# micro.net
KiCad netlist of a schematic drawn in EAGLE
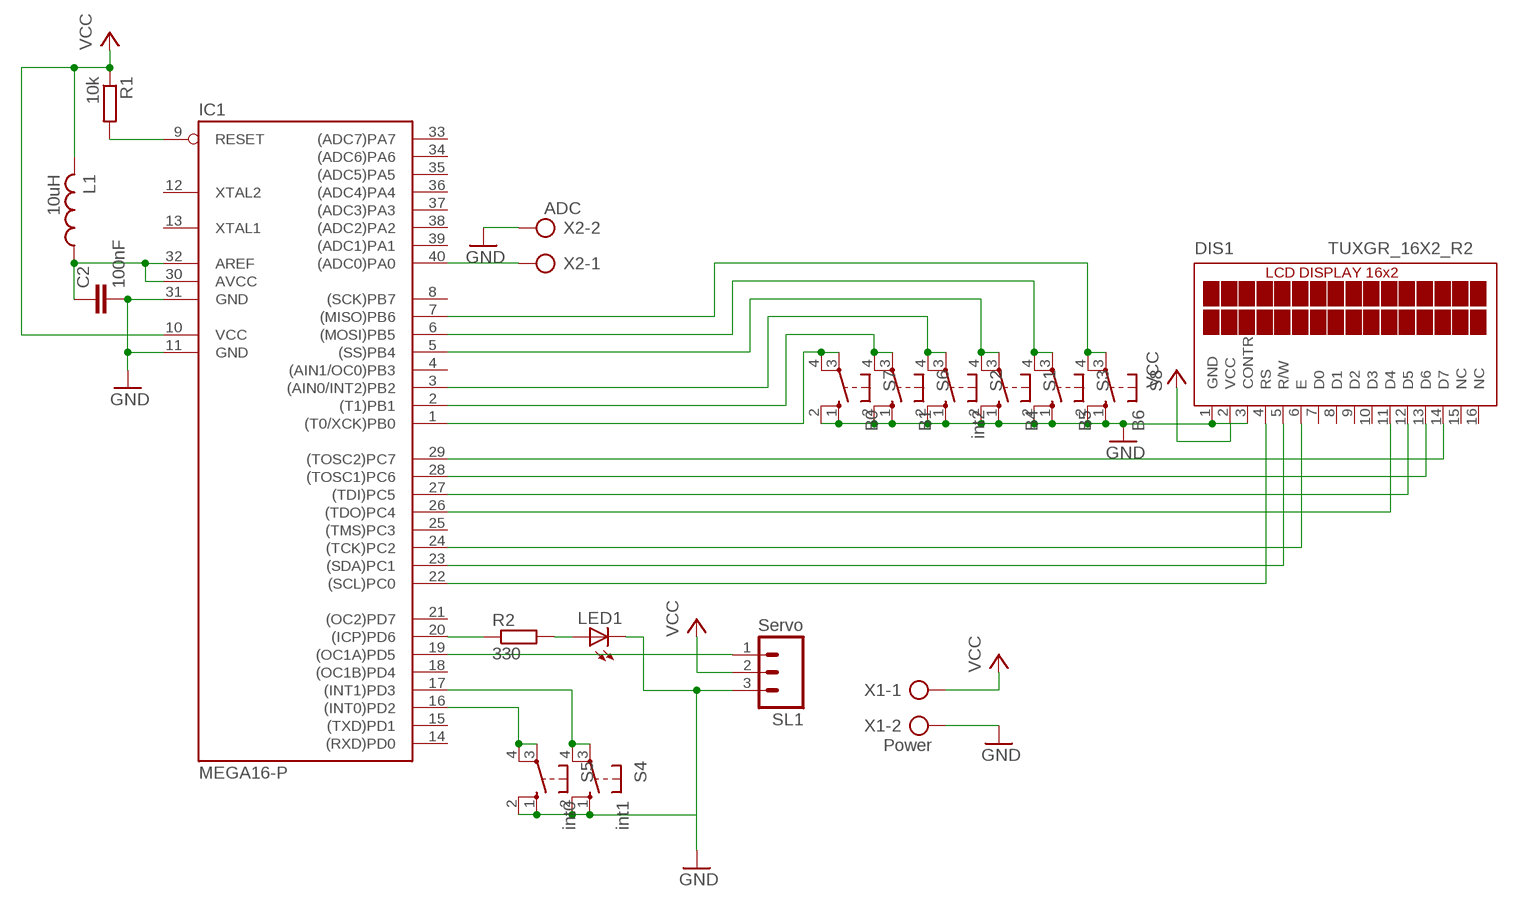
[diagram p0: schematic, sheet 1]

(export (version "E")
  (design (tool "Eeschema 10.0.6"))
  (components
    (comp (ref "C2")
      (value "100nF")
      (footprint "eagle-import:C025-024X044")
      (libsource (lib "eagle-import") (part "C-EU025-024X044"))
    )
    (comp (ref "DIS1")
      (value "TUXGR_16X2_R2")
      (footprint "eagle-import:TUXGR_16X2_R2")
      (libsource (lib "eagle-import") (part "TUXGR_16X2_R2"))
    )
    (comp (ref "IC1")
      (value "MEGA16-P")
      (footprint "eagle-import:DIL40")
      (fields (field (name "MPN") "ATMEGA16-16PU"))
      (libsource (lib "eagle-import") (part "MEGA16-P"))
    )
    (comp (ref "L1")
      (value "10uH")
      (footprint "eagle-import:0204_5")
      (libsource (lib "eagle-import") (part "L-US0204/5"))
    )
    (comp (ref "LED1")
      (value "LED5MM")
      (footprint "eagle-import:LED5MM")
      (libsource (lib "eagle-import") (part "LED5MM"))
    )
    (comp (ref "R1")
      (value "10k")
      (footprint "eagle-import:0204_7")
      (libsource (lib "eagle-import") (part "R-EU_0204/7"))
    )
    (comp (ref "R2")
      (value "330")
      (footprint "eagle-import:0204_7")
      (libsource (lib "eagle-import") (part "R-EU_0204/7"))
    )
    (comp (ref "S1")
      (value "B4")
      (footprint "eagle-import:B3F-10XX")
      (fields (field (name "MPN") "B3F-1000"))
      (libsource (lib "eagle-import") (part "10-XX"))
    )
    (comp (ref "S2")
      (value "int2")
      (footprint "eagle-import:B3F-10XX")
      (fields (field (name "MPN") "B3F-1000"))
      (libsource (lib "eagle-import") (part "10-XX"))
    )
    (comp (ref "S3")
      (value "B5")
      (footprint "eagle-import:B3F-10XX")
      (fields (field (name "MPN") "B3F-1000"))
      (libsource (lib "eagle-import") (part "10-XX"))
    )
    (comp (ref "S4")
      (value "int1")
      (footprint "eagle-import:B3F-10XX")
      (fields (field (name "MPN") "B3F-1000"))
      (libsource (lib "eagle-import") (part "10-XX"))
    )
    (comp (ref "S5")
      (value "int0")
      (footprint "eagle-import:B3F-10XX")
      (fields (field (name "MPN") "B3F-1000"))
      (libsource (lib "eagle-import") (part "10-XX"))
    )
    (comp (ref "S6")
      (value "B1")
      (footprint "eagle-import:B3F-10XX")
      (fields (field (name "MPN") "B3F-1000"))
      (libsource (lib "eagle-import") (part "10-XX"))
    )
    (comp (ref "S7")
      (value "B0")
      (footprint "eagle-import:B3F-10XX")
      (fields (field (name "MPN") "B3F-1000"))
      (libsource (lib "eagle-import") (part "10-XX"))
    )
    (comp (ref "S8")
      (value "B6")
      (footprint "eagle-import:B3F-10XX")
      (fields (field (name "MPN") "B3F-1000"))
      (libsource (lib "eagle-import") (part "10-XX"))
    )
    (comp (ref "SL1")
      (value "Servo")
      (footprint "eagle-import:03P")
      (libsource (lib "eagle-import") (part "M03"))
    )
    (comp (ref "X1")
      (value "Power")
      (footprint "eagle-import:AK300_2")
      (libsource (lib "eagle-import") (part "AK300/2"))
    )
    (comp (ref "X2")
      (value "ADC")
      (footprint "eagle-import:AK300_2")
      (libsource (lib "eagle-import") (part "AK300/2"))
    )
  )
  (nets
    (net (code "1") (name "GND") (class "Default")
      (node (ref "C2") (pin "2") (pinfunction "2_2") (pintype "passive"))
      (node (ref "DIS1") (pin "1") (pinfunction "GND_1") (pintype "power_in"))
      (node (ref "DIS1") (pin "3") (pinfunction "CONTR_3") (pintype "input"))
      (node (ref "IC1") (pin "11") (pinfunction "GND_11") (pintype "power_in"))
      (node (ref "IC1") (pin "31") (pinfunction "GND_31") (pintype "power_in"))
      (node (ref "LED1") (pin "K") (pinfunction "C_K") (pintype "passive"))
      (node (ref "S1") (pin "1") (pinfunction "S_1") (pintype "passive"))
      (node (ref "S1") (pin "2") (pinfunction "S1_2") (pintype "passive"))
      (node (ref "S2") (pin "1") (pinfunction "S_1") (pintype "passive"))
      (node (ref "S2") (pin "2") (pinfunction "S1_2") (pintype "passive"))
      (node (ref "S3") (pin "1") (pinfunction "S_1") (pintype "passive"))
      (node (ref "S3") (pin "2") (pinfunction "S1_2") (pintype "passive"))
      (node (ref "S4") (pin "1") (pinfunction "S_1") (pintype "passive"))
      (node (ref "S4") (pin "2") (pinfunction "S1_2") (pintype "passive"))
      (node (ref "S5") (pin "1") (pinfunction "S_1") (pintype "passive"))
      (node (ref "S5") (pin "2") (pinfunction "S1_2") (pintype "passive"))
      (node (ref "S6") (pin "1") (pinfunction "S_1") (pintype "passive"))
      (node (ref "S6") (pin "2") (pinfunction "S1_2") (pintype "passive"))
      (node (ref "S7") (pin "1") (pinfunction "S_1") (pintype "passive"))
      (node (ref "S7") (pin "2") (pinfunction "S1_2") (pintype "passive"))
      (node (ref "S8") (pin "1") (pinfunction "S_1") (pintype "passive"))
      (node (ref "S8") (pin "2") (pinfunction "S1_2") (pintype "passive"))
      (node (ref "SL1") (pin "3") (pinfunction "3_3") (pintype "passive"))
      (node (ref "X1") (pin "2") (pinfunction "KL_2") (pintype "passive"))
      (node (ref "X2") (pin "2") (pinfunction "KL_2") (pintype "passive"))
    )
    (net (code "2") (name "Net-(DIS1-D4)") (class "Default")
      (node (ref "DIS1") (pin "11") (pinfunction "D4_11") (pintype "input"))
      (node (ref "IC1") (pin "26") (pinfunction "(TDO)PC4_26") (pintype "bidirectional"))
    )
    (net (code "3") (name "Net-(DIS1-D5)") (class "Default")
      (node (ref "DIS1") (pin "12") (pinfunction "D5_12") (pintype "input"))
      (node (ref "IC1") (pin "27") (pinfunction "(TDI)PC5_27") (pintype "bidirectional"))
    )
    (net (code "4") (name "Net-(DIS1-D6)") (class "Default")
      (node (ref "DIS1") (pin "13") (pinfunction "D6_13") (pintype "input"))
      (node (ref "IC1") (pin "28") (pinfunction "(TOSC1)PC6_28") (pintype "bidirectional"))
    )
    (net (code "5") (name "Net-(DIS1-D7)") (class "Default")
      (node (ref "DIS1") (pin "14") (pinfunction "D7_14") (pintype "input"))
      (node (ref "IC1") (pin "29") (pinfunction "(TOSC2)PC7_29") (pintype "bidirectional"))
    )
    (net (code "6") (name "Net-(DIS1-E)") (class "Default")
      (node (ref "DIS1") (pin "6") (pinfunction "E_6") (pintype "input"))
      (node (ref "IC1") (pin "24") (pinfunction "(TCK)PC2_24") (pintype "bidirectional"))
    )
    (net (code "7") (name "Net-(DIS1-RS)") (class "Default")
      (node (ref "DIS1") (pin "4") (pinfunction "RS_4") (pintype "input"))
      (node (ref "IC1") (pin "22") (pinfunction "(SCL)PC0_22") (pintype "bidirectional"))
    )
    (net (code "8") (name "Net-(DIS1-R{slash}W)") (class "Default")
      (node (ref "DIS1") (pin "5") (pinfunction "R/W_5") (pintype "input"))
      (node (ref "IC1") (pin "23") (pinfunction "(SDA)PC1_23") (pintype "bidirectional"))
    )
    (net (code "9") (name "Net-(IC1-(ADC0)PA0)") (class "Default")
      (node (ref "IC1") (pin "40") (pinfunction "(ADC0)PA0_40") (pintype "bidirectional"))
      (node (ref "X2") (pin "1") (pinfunction "KL_1") (pintype "passive"))
    )
    (net (code "10") (name "Net-(IC1-(AIN0{slash}INT2)PB2)") (class "Default")
      (node (ref "IC1") (pin "3") (pinfunction "(AIN0/INT2)PB2_3") (pintype "bidirectional"))
      (node (ref "S2") (pin "3") (pinfunction "P_3") (pintype "passive"))
      (node (ref "S2") (pin "4") (pinfunction "P1_4") (pintype "passive"))
    )
    (net (code "11") (name "Net-(IC1-(ICP)PD6)") (class "Default")
      (node (ref "IC1") (pin "20") (pinfunction "(ICP)PD6_20") (pintype "bidirectional"))
      (node (ref "R2") (pin "1") (pinfunction "1_1") (pintype "passive"))
    )
    (net (code "12") (name "Net-(IC1-(INT0)PD2)") (class "Default")
      (node (ref "IC1") (pin "16") (pinfunction "(INT0)PD2_16") (pintype "bidirectional"))
      (node (ref "S5") (pin "3") (pinfunction "P_3") (pintype "passive"))
      (node (ref "S5") (pin "4") (pinfunction "P1_4") (pintype "passive"))
    )
    (net (code "13") (name "Net-(IC1-(INT1)PD3)") (class "Default")
      (node (ref "IC1") (pin "17") (pinfunction "(INT1)PD3_17") (pintype "bidirectional"))
      (node (ref "S4") (pin "3") (pinfunction "P_3") (pintype "passive"))
      (node (ref "S4") (pin "4") (pinfunction "P1_4") (pintype "passive"))
    )
    (net (code "14") (name "Net-(IC1-(MISO)PB6)") (class "Default")
      (node (ref "IC1") (pin "7") (pinfunction "(MISO)PB6_7") (pintype "bidirectional"))
      (node (ref "S8") (pin "3") (pinfunction "P_3") (pintype "passive"))
      (node (ref "S8") (pin "4") (pinfunction "P1_4") (pintype "passive"))
    )
    (net (code "15") (name "Net-(IC1-(MOSI)PB5)") (class "Default")
      (node (ref "IC1") (pin "6") (pinfunction "(MOSI)PB5_6") (pintype "bidirectional"))
      (node (ref "S3") (pin "3") (pinfunction "P_3") (pintype "passive"))
      (node (ref "S3") (pin "4") (pinfunction "P1_4") (pintype "passive"))
    )
    (net (code "16") (name "Net-(IC1-(OC1A)PD5)") (class "Default")
      (node (ref "IC1") (pin "19") (pinfunction "(OC1A)PD5_19") (pintype "bidirectional"))
      (node (ref "SL1") (pin "1") (pinfunction "1_1") (pintype "passive"))
    )
    (net (code "17") (name "Net-(IC1-(SS)PB4)") (class "Default")
      (node (ref "IC1") (pin "5") (pinfunction "(SS)PB4_5") (pintype "bidirectional"))
      (node (ref "S1") (pin "3") (pinfunction "P_3") (pintype "passive"))
      (node (ref "S1") (pin "4") (pinfunction "P1_4") (pintype "passive"))
    )
    (net (code "18") (name "Net-(IC1-(T0{slash}XCK)PB0)") (class "Default")
      (node (ref "IC1") (pin "1") (pinfunction "(T0/XCK)PB0_1") (pintype "bidirectional"))
      (node (ref "S7") (pin "3") (pinfunction "P_3") (pintype "passive"))
      (node (ref "S7") (pin "4") (pinfunction "P1_4") (pintype "passive"))
    )
    (net (code "19") (name "Net-(IC1-(T1)PB1)") (class "Default")
      (node (ref "IC1") (pin "2") (pinfunction "(T1)PB1_2") (pintype "bidirectional"))
      (node (ref "S6") (pin "3") (pinfunction "P_3") (pintype "passive"))
      (node (ref "S6") (pin "4") (pinfunction "P1_4") (pintype "passive"))
    )
    (net (code "20") (name "Net-(IC1-AREF)") (class "Default")
      (node (ref "C2") (pin "1") (pinfunction "1_1") (pintype "passive"))
      (node (ref "IC1") (pin "30") (pinfunction "AVCC_30") (pintype "power_in"))
      (node (ref "IC1") (pin "32") (pinfunction "AREF_32") (pintype "passive"))
      (node (ref "L1") (pin "1") (pinfunction "1_1") (pintype "passive"))
    )
    (net (code "21") (name "Net-(IC1-RESET)") (class "Default")
      (node (ref "IC1") (pin "9") (pinfunction "RESET_9") (pintype "input"))
      (node (ref "R1") (pin "2") (pinfunction "2_2") (pintype "passive"))
    )
    (net (code "22") (name "Net-(LED1-PadA)") (class "Default")
      (node (ref "LED1") (pin "A") (pinfunction "A_A") (pintype "passive"))
      (node (ref "R2") (pin "2") (pinfunction "2_2") (pintype "passive"))
    )
    (net (code "23") (name "VCC") (class "Default")
      (node (ref "DIS1") (pin "2") (pinfunction "VCC_2") (pintype "power_in"))
      (node (ref "IC1") (pin "10") (pinfunction "VCC_10") (pintype "power_in"))
      (node (ref "L1") (pin "2") (pinfunction "2_2") (pintype "passive"))
      (node (ref "R1") (pin "1") (pinfunction "1_1") (pintype "passive"))
      (node (ref "SL1") (pin "2") (pinfunction "2_2") (pintype "passive"))
      (node (ref "X1") (pin "1") (pinfunction "KL_1") (pintype "passive"))
    )
    (net (code "24") (name "unconnected-(DIS1-D0-Pad7)") (class "Default")
      (node (ref "DIS1") (pin "7") (pinfunction "D0_7") (pintype "input"))
    )
    (net (code "25") (name "unconnected-(DIS1-D1-Pad8)") (class "Default")
      (node (ref "DIS1") (pin "8") (pinfunction "D1_8") (pintype "input"))
    )
    (net (code "26") (name "unconnected-(DIS1-D2-Pad9)") (class "Default")
      (node (ref "DIS1") (pin "9") (pinfunction "D2_9") (pintype "input"))
    )
    (net (code "27") (name "unconnected-(DIS1-D3-Pad10)") (class "Default")
      (node (ref "DIS1") (pin "10") (pinfunction "D3_10") (pintype "input"))
    )
    (net (code "28") (name "unconnected-(DIS1-NC-Pad15)") (class "Default")
      (node (ref "DIS1") (pin "15") (pinfunction "NC_15") (pintype "no_connect"))
    )
    (net (code "29") (name "unconnected-(DIS1-NC-Pad16)") (class "Default")
      (node (ref "DIS1") (pin "16") (pinfunction "NC_16") (pintype "no_connect"))
    )
    (net (code "30") (name "unconnected-(IC1-(ADC1)PA1-Pad39)") (class "Default")
      (node (ref "IC1") (pin "39") (pinfunction "(ADC1)PA1_39") (pintype "bidirectional"))
    )
    (net (code "31") (name "unconnected-(IC1-(ADC2)PA2-Pad38)") (class "Default")
      (node (ref "IC1") (pin "38") (pinfunction "(ADC2)PA2_38") (pintype "bidirectional"))
    )
    (net (code "32") (name "unconnected-(IC1-(ADC3)PA3-Pad37)") (class "Default")
      (node (ref "IC1") (pin "37") (pinfunction "(ADC3)PA3_37") (pintype "bidirectional"))
    )
    (net (code "33") (name "unconnected-(IC1-(ADC4)PA4-Pad36)") (class "Default")
      (node (ref "IC1") (pin "36") (pinfunction "(ADC4)PA4_36") (pintype "bidirectional"))
    )
    (net (code "34") (name "unconnected-(IC1-(ADC5)PA5-Pad35)") (class "Default")
      (node (ref "IC1") (pin "35") (pinfunction "(ADC5)PA5_35") (pintype "bidirectional"))
    )
    (net (code "35") (name "unconnected-(IC1-(ADC6)PA6-Pad34)") (class "Default")
      (node (ref "IC1") (pin "34") (pinfunction "(ADC6)PA6_34") (pintype "bidirectional"))
    )
    (net (code "36") (name "unconnected-(IC1-(ADC7)PA7-Pad33)") (class "Default")
      (node (ref "IC1") (pin "33") (pinfunction "(ADC7)PA7_33") (pintype "bidirectional"))
    )
    (net (code "37") (name "unconnected-(IC1-(AIN1{slash}OC0)PB3-Pad4)") (class "Default")
      (node (ref "IC1") (pin "4") (pinfunction "(AIN1/OC0)PB3_4") (pintype "bidirectional"))
    )
    (net (code "38") (name "unconnected-(IC1-(OC1B)PD4-Pad18)") (class "Default")
      (node (ref "IC1") (pin "18") (pinfunction "(OC1B)PD4_18") (pintype "bidirectional"))
    )
    (net (code "39") (name "unconnected-(IC1-(OC2)PD7-Pad21)") (class "Default")
      (node (ref "IC1") (pin "21") (pinfunction "(OC2)PD7_21") (pintype "bidirectional"))
    )
    (net (code "40") (name "unconnected-(IC1-(RXD)PD0-Pad14)") (class "Default")
      (node (ref "IC1") (pin "14") (pinfunction "(RXD)PD0_14") (pintype "bidirectional"))
    )
    (net (code "41") (name "unconnected-(IC1-(SCK)PB7-Pad8)") (class "Default")
      (node (ref "IC1") (pin "8") (pinfunction "(SCK)PB7_8") (pintype "bidirectional"))
    )
    (net (code "42") (name "unconnected-(IC1-(TMS)PC3-Pad25)") (class "Default")
      (node (ref "IC1") (pin "25") (pinfunction "(TMS)PC3_25") (pintype "bidirectional"))
    )
    (net (code "43") (name "unconnected-(IC1-(TXD)PD1-Pad15)") (class "Default")
      (node (ref "IC1") (pin "15") (pinfunction "(TXD)PD1_15") (pintype "bidirectional"))
    )
    (net (code "44") (name "unconnected-(IC1-XTAL1-Pad13)") (class "Default")
      (node (ref "IC1") (pin "13") (pinfunction "XTAL1_13") (pintype "bidirectional"))
    )
    (net (code "45") (name "unconnected-(IC1-XTAL2-Pad12)") (class "Default")
      (node (ref "IC1") (pin "12") (pinfunction "XTAL2_12") (pintype "bidirectional"))
    )
  )
)
